# evpr_mini.net
KiCad netlist of a schematic drawn in EAGLE
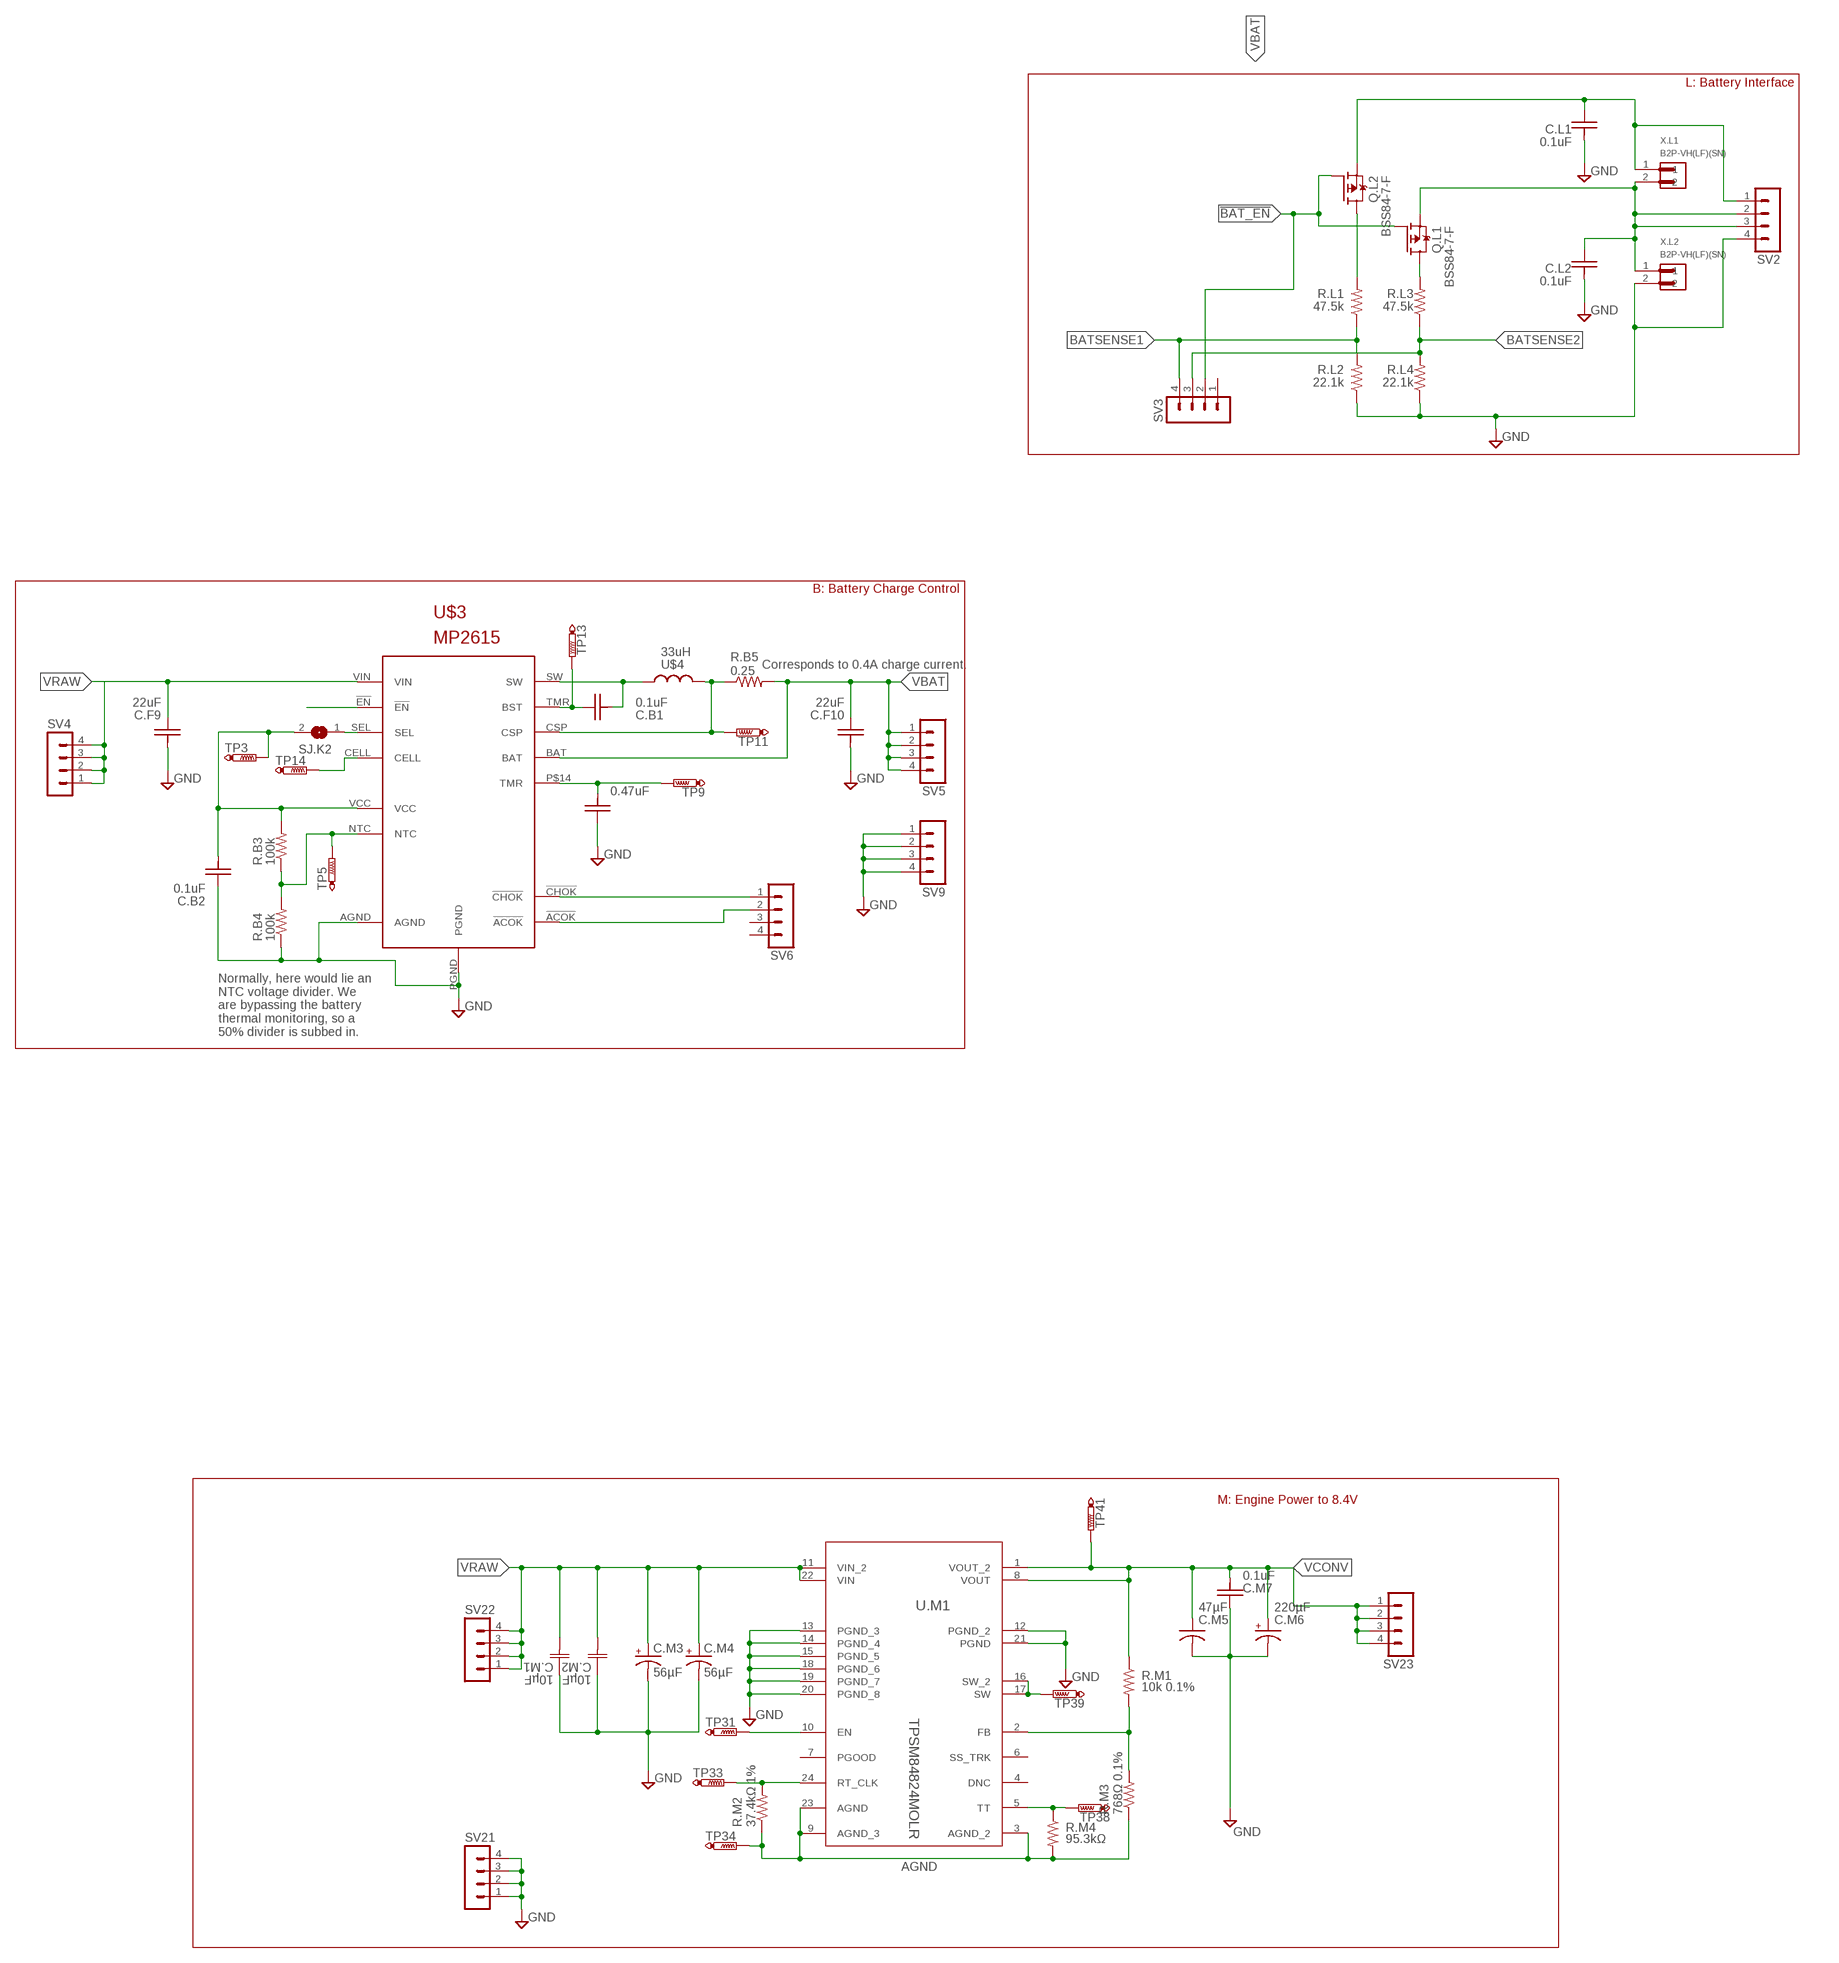
[diagram p0: schematic, sheet 1, part 1 of 2]
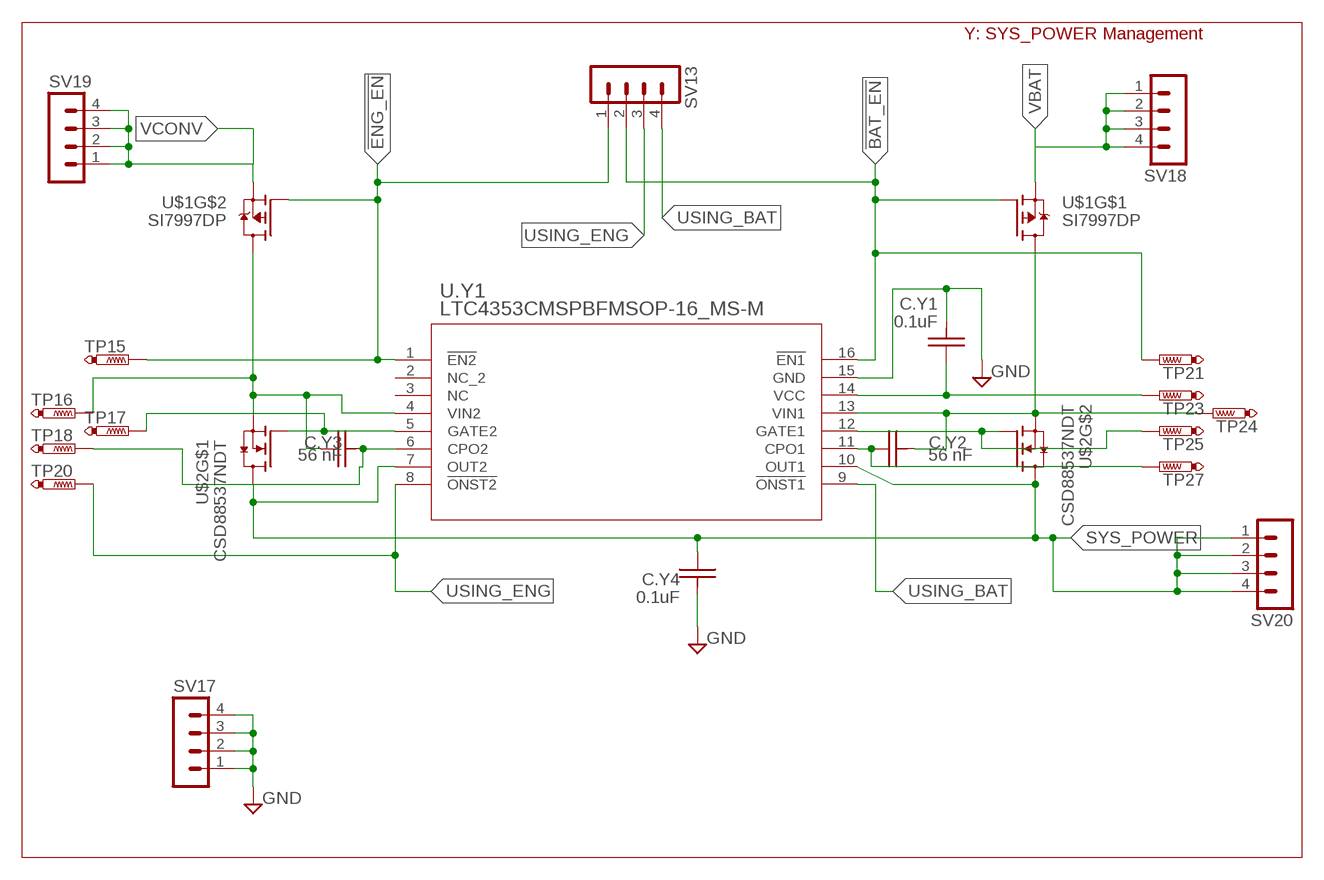
[diagram p1: schematic, sheet 1, part 2 of 2]

(export (version "E")
  (design (tool "Eeschema 10.0.6"))
  (components
    (comp (ref "C.B1")
      (value "0.1uF")
      (footprint "eagle-import:C0603")
      (libsource (lib "eagle-import") (part "C0603"))
    )
    (comp (ref "C.B2")
      (value "0.1uF")
      (footprint "eagle-import:C0603")
      (libsource (lib "eagle-import") (part "C0603"))
    )
    (comp (ref "C.F9")
      (value "22uF")
      (footprint "eagle-import:C0603")
      (libsource (lib "eagle-import") (part "C0603"))
    )
    (comp (ref "C.F10")
      (value "22uF")
      (footprint "eagle-import:C0603")
      (libsource (lib "eagle-import") (part "C0603"))
    )
    (comp (ref "C.J3")
      (value "0.47uF")
      (footprint "eagle-import:C0603")
      (libsource (lib "eagle-import") (part "C0603"))
    )
    (comp (ref "C.L1")
      (value "0.1uF")
      (footprint "eagle-import:C0603")
      (libsource (lib "eagle-import") (part "C0603"))
    )
    (comp (ref "C.L2")
      (value "0.1uF")
      (footprint "eagle-import:C0603")
      (libsource (lib "eagle-import") (part "C0603"))
    )
    (comp (ref "C.M1")
      (value "10µF")
      (footprint "eagle-import:CAP_3225")
      (libsource (lib "eagle-import") (part "C3225X7R1E106K250AC"))
    )
    (comp (ref "C.M2")
      (value "10µF")
      (footprint "eagle-import:CAP_3225")
      (libsource (lib "eagle-import") (part "C3225X7R1E106K250AC"))
    )
    (comp (ref "C.M3")
      (value "56µF")
      (footprint "eagle-import:OSCON_SVPF_6.3MM")
      (libsource (lib "eagle-import") (part "6.3MMCAP"))
    )
    (comp (ref "C.M4")
      (value "56µF")
      (footprint "eagle-import:OSCON_SVPF_6.3MM")
      (libsource (lib "eagle-import") (part "6.3MMCAP"))
    )
    (comp (ref "C.M5")
      (value "47µF")
      (footprint "eagle-import:C1210")
      (libsource (lib "eagle-import") (part "C-USC1210"))
    )
    (comp (ref "C.M6")
      (value "220µF")
      (footprint "eagle-import:C6CYLCAP")
      (libsource (lib "eagle-import") (part "WURTH875115352003"))
    )
    (comp (ref "C.M7")
      (value "0.1uF")
      (footprint "eagle-import:C0603")
      (libsource (lib "eagle-import") (part "C0603"))
    )
    (comp (ref "C.Y1")
      (value "0.1uF")
      (footprint "eagle-import:C0603")
      (libsource (lib "eagle-import") (part "C0603"))
    )
    (comp (ref "C.Y2")
      (value "56 nF")
      (footprint "eagle-import:C0603")
      (libsource (lib "eagle-import") (part "C0603"))
    )
    (comp (ref "C.Y3")
      (value "56 nF")
      (footprint "eagle-import:C0603")
      (libsource (lib "eagle-import") (part "C0603"))
    )
    (comp (ref "C.Y4")
      (value "0.1uF")
      (footprint "eagle-import:C0603")
      (libsource (lib "eagle-import") (part "C0603"))
    )
    (comp (ref "Q.L1")
      (value "BSS84-7-F")
      (footprint "eagle-import:SOT23")
      (libsource (lib "eagle-import") (part "BSS84-7-F"))
    )
    (comp (ref "Q.L2")
      (value "BSS84-7-F")
      (footprint "eagle-import:SOT23")
      (libsource (lib "eagle-import") (part "BSS84-7-F"))
    )
    (comp (ref "R.B3")
      (value "100k")
      (footprint "eagle-import:R0603")
      (libsource (lib "eagle-import") (part "R0603"))
    )
    (comp (ref "R.B4")
      (value "100k")
      (footprint "eagle-import:R0603")
      (libsource (lib "eagle-import") (part "R0603"))
    )
    (comp (ref "R.B5")
      (value "0.25")
      (footprint "eagle-import:R0603")
      (libsource (lib "eagle-import") (part "R0603"))
    )
    (comp (ref "R.L1")
      (value "47.5k")
      (footprint "eagle-import:R0603")
      (libsource (lib "eagle-import") (part "R0603"))
    )
    (comp (ref "R.L2")
      (value "22.1k")
      (footprint "eagle-import:R0603")
      (libsource (lib "eagle-import") (part "R0603"))
    )
    (comp (ref "R.L3")
      (value "47.5k")
      (footprint "eagle-import:R0603")
      (libsource (lib "eagle-import") (part "R0603"))
    )
    (comp (ref "R.L4")
      (value "22.1k")
      (footprint "eagle-import:R0603")
      (libsource (lib "eagle-import") (part "R0603"))
    )
    (comp (ref "R.M1")
      (value "10k 0.1%")
      (footprint "eagle-import:R0603")
      (libsource (lib "eagle-import") (part "R0603"))
    )
    (comp (ref "R.M2")
      (value "37.4kΩ 1%")
      (footprint "eagle-import:R0603")
      (libsource (lib "eagle-import") (part "R0603"))
    )
    (comp (ref "R.M3")
      (value "768Ω 0.1%")
      (footprint "eagle-import:R0603")
      (libsource (lib "eagle-import") (part "R0603"))
    )
    (comp (ref "R.M4")
      (value "95.3kΩ")
      (footprint "eagle-import:R0603")
      (libsource (lib "eagle-import") (part "R0603"))
    )
    (comp (ref "SJ.K2")
      (value "SJ")
      (footprint "eagle-import:SJ")
      (libsource (lib "eagle-import") (part "SJ"))
    )
    (comp (ref "SV2")
      (value "MA04-1")
      (footprint "eagle-import:MA04-1")
      (libsource (lib "eagle-import") (part "MA04-1"))
    )
    (comp (ref "SV3")
      (value "MA04-1")
      (footprint "eagle-import:MA04-1")
      (libsource (lib "eagle-import") (part "MA04-1"))
    )
    (comp (ref "SV4")
      (value "MA04-1")
      (footprint "eagle-import:MA04-1")
      (libsource (lib "eagle-import") (part "MA04-1"))
    )
    (comp (ref "SV5")
      (value "MA04-1")
      (footprint "eagle-import:MA04-1")
      (libsource (lib "eagle-import") (part "MA04-1"))
    )
    (comp (ref "SV6")
      (value "MA04-1")
      (footprint "eagle-import:MA04-1")
      (libsource (lib "eagle-import") (part "MA04-1"))
    )
    (comp (ref "SV9")
      (value "MA04-1")
      (footprint "eagle-import:MA04-1")
      (libsource (lib "eagle-import") (part "MA04-1"))
    )
    (comp (ref "SV13")
      (value "MA04-1")
      (footprint "eagle-import:MA04-1")
      (libsource (lib "eagle-import") (part "MA04-1"))
    )
    (comp (ref "SV17")
      (value "MA04-1")
      (footprint "eagle-import:MA04-1")
      (libsource (lib "eagle-import") (part "MA04-1"))
    )
    (comp (ref "SV18")
      (value "MA04-1")
      (footprint "eagle-import:MA04-1")
      (libsource (lib "eagle-import") (part "MA04-1"))
    )
    (comp (ref "SV19")
      (value "MA04-1")
      (footprint "eagle-import:MA04-1")
      (libsource (lib "eagle-import") (part "MA04-1"))
    )
    (comp (ref "SV20")
      (value "MA04-1")
      (footprint "eagle-import:MA04-1")
      (libsource (lib "eagle-import") (part "MA04-1"))
    )
    (comp (ref "SV21")
      (value "MA04-1")
      (footprint "eagle-import:MA04-1")
      (libsource (lib "eagle-import") (part "MA04-1"))
    )
    (comp (ref "SV22")
      (value "MA04-1")
      (footprint "eagle-import:MA04-1")
      (libsource (lib "eagle-import") (part "MA04-1"))
    )
    (comp (ref "SV23")
      (value "MA04-1")
      (footprint "eagle-import:MA04-1")
      (libsource (lib "eagle-import") (part "MA04-1"))
    )
    (comp (ref "TP3")
      (value "PTR1TP10R")
      (footprint "eagle-import:TP10R")
      (libsource (lib "eagle-import") (part "PTR1TP10R"))
    )
    (comp (ref "TP5")
      (value "PTR1TP10R")
      (footprint "eagle-import:TP10R")
      (libsource (lib "eagle-import") (part "PTR1TP10R"))
    )
    (comp (ref "TP9")
      (value "PTR1TP10R")
      (footprint "eagle-import:TP10R")
      (libsource (lib "eagle-import") (part "PTR1TP10R"))
    )
    (comp (ref "TP11")
      (value "PTR1TP10R")
      (footprint "eagle-import:TP10R")
      (libsource (lib "eagle-import") (part "PTR1TP10R"))
    )
    (comp (ref "TP13")
      (value "PTR1TP10R")
      (footprint "eagle-import:TP10R")
      (libsource (lib "eagle-import") (part "PTR1TP10R"))
    )
    (comp (ref "TP14")
      (value "PTR1TP10R")
      (footprint "eagle-import:TP10R")
      (libsource (lib "eagle-import") (part "PTR1TP10R"))
    )
    (comp (ref "TP15")
      (value "PTR1TP10R")
      (footprint "eagle-import:TP10R")
      (libsource (lib "eagle-import") (part "PTR1TP10R"))
    )
    (comp (ref "TP16")
      (value "PTR1TP10R")
      (footprint "eagle-import:TP10R")
      (libsource (lib "eagle-import") (part "PTR1TP10R"))
    )
    (comp (ref "TP17")
      (value "PTR1TP10R")
      (footprint "eagle-import:TP10R")
      (libsource (lib "eagle-import") (part "PTR1TP10R"))
    )
    (comp (ref "TP18")
      (value "PTR1TP10R")
      (footprint "eagle-import:TP10R")
      (libsource (lib "eagle-import") (part "PTR1TP10R"))
    )
    (comp (ref "TP20")
      (value "PTR1TP10R")
      (footprint "eagle-import:TP10R")
      (libsource (lib "eagle-import") (part "PTR1TP10R"))
    )
    (comp (ref "TP21")
      (value "PTR1TP10R")
      (footprint "eagle-import:TP10R")
      (libsource (lib "eagle-import") (part "PTR1TP10R"))
    )
    (comp (ref "TP23")
      (value "PTR1TP10R")
      (footprint "eagle-import:TP10R")
      (libsource (lib "eagle-import") (part "PTR1TP10R"))
    )
    (comp (ref "TP24")
      (value "PTR1TP10R")
      (footprint "eagle-import:TP10R")
      (libsource (lib "eagle-import") (part "PTR1TP10R"))
    )
    (comp (ref "TP25")
      (value "PTR1TP10R")
      (footprint "eagle-import:TP10R")
      (libsource (lib "eagle-import") (part "PTR1TP10R"))
    )
    (comp (ref "TP27")
      (value "PTR1TP10R")
      (footprint "eagle-import:TP10R")
      (libsource (lib "eagle-import") (part "PTR1TP10R"))
    )
    (comp (ref "TP31")
      (value "PTR1TP10R")
      (footprint "eagle-import:TP10R")
      (libsource (lib "eagle-import") (part "PTR1TP10R"))
    )
    (comp (ref "TP33")
      (value "PTR1TP10R")
      (footprint "eagle-import:TP10R")
      (libsource (lib "eagle-import") (part "PTR1TP10R"))
    )
    (comp (ref "TP34")
      (value "PTR1TP10R")
      (footprint "eagle-import:TP10R")
      (libsource (lib "eagle-import") (part "PTR1TP10R"))
    )
    (comp (ref "TP38")
      (value "PTR1TP10R")
      (footprint "eagle-import:TP10R")
      (libsource (lib "eagle-import") (part "PTR1TP10R"))
    )
    (comp (ref "TP39")
      (value "PTR1TP10R")
      (footprint "eagle-import:TP10R")
      (libsource (lib "eagle-import") (part "PTR1TP10R"))
    )
    (comp (ref "TP41")
      (value "PTR1TP10R")
      (footprint "eagle-import:TP10R")
      (libsource (lib "eagle-import") (part "PTR1TP10R"))
    )
    (comp (ref "U$1")
      (value "SI7997DP")
      (footprint "eagle-import:POWERPAK_SO8DUAL")
      (libsource (lib "eagle-import") (part "SI7997DP"))
    )
    (comp (ref "U$2")
      (value "CSD88537NDT")
      (footprint "eagle-import:SOIC8")
      (libsource (lib "eagle-import") (part "CSD88537NDT"))
    )
    (comp (ref "U$3")
      (value "MP2615")
      (footprint "eagle-import:QFN16")
      (libsource (lib "eagle-import") (part "MP2615"))
    )
    (comp (ref "U$4")
      (value "33uH")
      (footprint "eagle-import:SRN5040TA")
      (libsource (lib "eagle-import") (part "SRN5040TA-330M"))
    )
    (comp (ref "U.M1")
      (value "TPSM84824MOLR")
      (footprint "eagle-import:MOL0024A")
      (libsource (lib "eagle-import") (part "TPSM84824MOLR"))
    )
    (comp (ref "U.Y1")
      (value "LTC4353CMSPBFMSOP-16_MS-M")
      (footprint "eagle-import:MSOP-16_MS-M")
      (fields (field (name "MANUFACTURER_PART_NUMBER") "LTC4353CMS#PBF"))
      (libsource (lib "eagle-import") (part "LTC4353CMSPBFMSOP-16_MS-M"))
    )
    (comp (ref "X.L1")
      (value "B2P-VH(LF)(SN)")
      (footprint "eagle-import:JST_B2P-VH(LF)(SN)")
      (fields (field (name "MF") "JST Sales") (field (name "MP") "B2P-VH_LF__SN_"))
      (libsource (lib "eagle-import") (part "B2P-VH(LF)(SN)"))
    )
    (comp (ref "X.L2")
      (value "B2P-VH(LF)(SN)")
      (footprint "eagle-import:JST_B2P-VH(LF)(SN)")
      (fields (field (name "MF") "JST Sales") (field (name "MP") "B2P-VH_LF__SN_"))
      (libsource (lib "eagle-import") (part "B2P-VH(LF)(SN)"))
    )
  )
  (nets
    (net (code "1") (name "/AGND") (class "Default")
      (node (ref "R.M2") (pin "1") (pinfunction "1_1") (pintype "passive"))
      (node (ref "R.M3") (pin "1") (pinfunction "1_1") (pintype "passive"))
      (node (ref "R.M4") (pin "2") (pinfunction "2_2") (pintype "passive"))
      (node (ref "TP34") (pin "TP") (pinfunction "TP_TP") (pintype "input"))
      (node (ref "U.M1") (pin "23") (pinfunction "AGND_23") (pintype "power_in"))
      (node (ref "U.M1") (pin "3") (pinfunction "AGND_2_3") (pintype "power_in"))
      (node (ref "U.M1") (pin "9") (pinfunction "AGND_3_9") (pintype "power_in"))
    )
    (net (code "2") (name "/~{BAT_EN}") (class "Default")
      (node (ref "Q.L1") (pin "1") (pinfunction "G_1") (pintype "passive"))
      (node (ref "Q.L2") (pin "1") (pinfunction "G_1") (pintype "passive"))
      (node (ref "SV13") (pin "2") (pinfunction "2_2") (pintype "passive"))
      (node (ref "SV3") (pin "2") (pinfunction "2_2") (pintype "passive"))
      (node (ref "TP21") (pin "TP") (pinfunction "TP_TP") (pintype "input"))
      (node (ref "U$1") (pin "P$2") (pinfunction "G_P$2") (pintype "passive"))
      (node (ref "U.Y1") (pin "16") (pinfunction "~{EN1}_16") (pintype "input"))
    )
    (net (code "3") (name "/~{ENG_EN}") (class "Default")
      (node (ref "SV13") (pin "1") (pinfunction "1_1") (pintype "passive"))
      (node (ref "TP15") (pin "TP") (pinfunction "TP_TP") (pintype "input"))
      (node (ref "U$1") (pin "P$4") (pinfunction "G_P$4") (pintype "passive"))
      (node (ref "U.Y1") (pin "1") (pinfunction "~{EN2}_1") (pintype "input"))
    )
    (net (code "4") (name "BATSENSE1") (class "Default")
      (node (ref "R.L1") (pin "1") (pinfunction "1_1") (pintype "passive"))
      (node (ref "R.L2") (pin "2") (pinfunction "2_2") (pintype "passive"))
      (node (ref "SV3") (pin "4") (pinfunction "4_4") (pintype "passive"))
    )
    (net (code "5") (name "BATSENSE2") (class "Default")
      (node (ref "R.L3") (pin "1") (pinfunction "1_1") (pintype "passive"))
      (node (ref "R.L4") (pin "2") (pinfunction "2_2") (pintype "passive"))
      (node (ref "SV3") (pin "3") (pinfunction "3_3") (pintype "passive"))
    )
    (net (code "6") (name "GND") (class "Default")
      (node (ref "C.B2") (pin "1") (pinfunction "1_1") (pintype "passive"))
      (node (ref "C.F10") (pin "2") (pinfunction "2_2") (pintype "passive"))
      (node (ref "C.F9") (pin "2") (pinfunction "2_2") (pintype "passive"))
      (node (ref "C.J3") (pin "1") (pinfunction "1_1") (pintype "passive"))
      (node (ref "C.L1") (pin "2") (pinfunction "2_2") (pintype "passive"))
      (node (ref "C.L2") (pin "2") (pinfunction "2_2") (pintype "passive"))
      (node (ref "C.M1") (pin "1") (pinfunction "1_1") (pintype "passive"))
      (node (ref "C.M2") (pin "1") (pinfunction "1_1") (pintype "passive"))
      (node (ref "C.M3") (pin "-") (pinfunction "-_-") (pintype "passive"))
      (node (ref "C.M4") (pin "-") (pinfunction "-_-") (pintype "passive"))
      (node (ref "C.M5") (pin "2") (pinfunction "2_2") (pintype "passive"))
      (node (ref "C.M6") (pin "P$1") (pinfunction "-_P$1") (pintype "passive"))
      (node (ref "C.M7") (pin "1") (pinfunction "1_1") (pintype "passive"))
      (node (ref "C.Y1") (pin "2") (pinfunction "2_2") (pintype "passive"))
      (node (ref "C.Y4") (pin "2") (pinfunction "2_2") (pintype "passive"))
      (node (ref "R.B4") (pin "1") (pinfunction "1_1") (pintype "passive"))
      (node (ref "R.L2") (pin "1") (pinfunction "1_1") (pintype "passive"))
      (node (ref "R.L4") (pin "1") (pinfunction "1_1") (pintype "passive"))
      (node (ref "SV17") (pin "1") (pinfunction "1_1") (pintype "passive"))
      (node (ref "SV17") (pin "2") (pinfunction "2_2") (pintype "passive"))
      (node (ref "SV17") (pin "3") (pinfunction "3_3") (pintype "passive"))
      (node (ref "SV17") (pin "4") (pinfunction "4_4") (pintype "passive"))
      (node (ref "SV2") (pin "4") (pinfunction "4_4") (pintype "passive"))
      (node (ref "SV21") (pin "1") (pinfunction "1_1") (pintype "passive"))
      (node (ref "SV21") (pin "2") (pinfunction "2_2") (pintype "passive"))
      (node (ref "SV21") (pin "3") (pinfunction "3_3") (pintype "passive"))
      (node (ref "SV21") (pin "4") (pinfunction "4_4") (pintype "passive"))
      (node (ref "SV9") (pin "1") (pinfunction "1_1") (pintype "passive"))
      (node (ref "SV9") (pin "2") (pinfunction "2_2") (pintype "passive"))
      (node (ref "SV9") (pin "3") (pinfunction "3_3") (pintype "passive"))
      (node (ref "SV9") (pin "4") (pinfunction "4_4") (pintype "passive"))
      (node (ref "U$3") (pin "AGND") (pinfunction "AGND_AGND") (pintype "bidirectional"))
      (node (ref "U$3") (pin "PGND") (pinfunction "PGND_PGND") (pintype "bidirectional"))
      (node (ref "U.M1") (pin "12") (pinfunction "PGND_2_12") (pintype "power_in"))
      (node (ref "U.M1") (pin "13") (pinfunction "PGND_3_13") (pintype "power_in"))
      (node (ref "U.M1") (pin "14") (pinfunction "PGND_4_14") (pintype "power_in"))
      (node (ref "U.M1") (pin "15") (pinfunction "PGND_5_15") (pintype "power_in"))
      (node (ref "U.M1") (pin "18") (pinfunction "PGND_6_18") (pintype "power_in"))
      (node (ref "U.M1") (pin "19") (pinfunction "PGND_7_19") (pintype "power_in"))
      (node (ref "U.M1") (pin "20") (pinfunction "PGND_8_20") (pintype "power_in"))
      (node (ref "U.M1") (pin "21") (pinfunction "PGND_21") (pintype "power_in"))
      (node (ref "U.Y1") (pin "15") (pinfunction "GND_15") (pintype "power_in"))
      (node (ref "X.L2") (pin "2") (pinfunction "2_2") (pintype "passive"))
    )
    (net (code "7") (name "Net-(C.B2-Pad2)") (class "Default")
      (node (ref "C.B2") (pin "2") (pinfunction "2_2") (pintype "passive"))
      (node (ref "R.B3") (pin "2") (pinfunction "2_2") (pintype "passive"))
      (node (ref "SJ.K2") (pin "2") (pinfunction "2_2") (pintype "passive"))
      (node (ref "TP3") (pin "TP") (pinfunction "TP_TP") (pintype "input"))
      (node (ref "U$3") (pin "VCC") (pinfunction "VCC_VCC") (pintype "bidirectional"))
    )
    (net (code "8") (name "Net-(Q.L1-D)") (class "Default")
      (node (ref "Q.L1") (pin "3") (pinfunction "D_3") (pintype "passive"))
      (node (ref "R.L3") (pin "2") (pinfunction "2_2") (pintype "passive"))
    )
    (net (code "9") (name "Net-(Q.L1-S)") (class "Default")
      (node (ref "C.L2") (pin "1") (pinfunction "1_1") (pintype "passive"))
      (node (ref "Q.L1") (pin "2") (pinfunction "S_2") (pintype "passive"))
      (node (ref "SV2") (pin "2") (pinfunction "2_2") (pintype "passive"))
      (node (ref "SV2") (pin "3") (pinfunction "3_3") (pintype "passive"))
      (node (ref "X.L1") (pin "2") (pinfunction "2_2") (pintype "passive"))
      (node (ref "X.L2") (pin "1") (pinfunction "1_1") (pintype "passive"))
    )
    (net (code "10") (name "Net-(Q.L2-D)") (class "Default")
      (node (ref "Q.L2") (pin "3") (pinfunction "D_3") (pintype "passive"))
      (node (ref "R.L1") (pin "2") (pinfunction "2_2") (pintype "passive"))
    )
    (net (code "11") (name "Net-(R.B3-Pad1)") (class "Default")
      (node (ref "R.B3") (pin "1") (pinfunction "1_1") (pintype "passive"))
      (node (ref "R.B4") (pin "2") (pinfunction "2_2") (pintype "passive"))
      (node (ref "TP5") (pin "TP") (pinfunction "TP_TP") (pintype "input"))
      (node (ref "U$3") (pin "NTC") (pinfunction "NTC_NTC") (pintype "bidirectional"))
    )
    (net (code "12") (name "Net-(SJ.K2-Pad1)") (class "Default")
      (node (ref "SJ.K2") (pin "1") (pinfunction "1_1") (pintype "passive"))
      (node (ref "U$3") (pin "SEL") (pinfunction "SEL_SEL") (pintype "bidirectional"))
    )
    (net (code "13") (name "Net-(TP14-PadTP)") (class "Default")
      (node (ref "TP14") (pin "TP") (pinfunction "TP_TP") (pintype "input"))
      (node (ref "U$3") (pin "CELL") (pinfunction "CELL_CELL") (pintype "bidirectional"))
    )
    (net (code "14") (name "Net-(U$1A-D)") (class "Default")
      (node (ref "C.Y2") (pin "2") (pinfunction "2_2") (pintype "passive"))
      (node (ref "TP24") (pin "TP") (pinfunction "TP_TP") (pintype "input"))
      (node (ref "U$1") (pin "D$1B") (pinfunction "D_D$1B") (pintype "passive"))
      (node (ref "U$2") (pin "3") (pinfunction "S_3") (pintype "passive"))
      (node (ref "U.Y1") (pin "13") (pinfunction "VIN1_13") (pintype "input"))
    )
    (net (code "15") (name "Net-(U$1B-D)") (class "Default")
      (node (ref "C.Y3") (pin "1") (pinfunction "1_1") (pintype "passive"))
      (node (ref "TP16") (pin "TP") (pinfunction "TP_TP") (pintype "input"))
      (node (ref "U$1") (pin "D$2A") (pinfunction "D_D$2A") (pintype "passive"))
      (node (ref "U$2") (pin "1") (pinfunction "S_1") (pintype "passive"))
      (node (ref "U.Y1") (pin "4") (pinfunction "VIN2_4") (pintype "input"))
    )
    (net (code "16") (name "Net-(U$2A-G)") (class "Default")
      (node (ref "TP17") (pin "TP") (pinfunction "TP_TP") (pintype "input"))
      (node (ref "U$2") (pin "2") (pinfunction "G_2") (pintype "passive"))
      (node (ref "U.Y1") (pin "5") (pinfunction "GATE2_5") (pintype "output"))
    )
    (net (code "17") (name "Net-(U$2B-G)") (class "Default")
      (node (ref "TP25") (pin "TP") (pinfunction "TP_TP") (pintype "input"))
      (node (ref "U$2") (pin "4") (pinfunction "G_4") (pintype "passive"))
      (node (ref "U.Y1") (pin "12") (pinfunction "GATE1_12") (pintype "output"))
    )
    (net (code "18") (name "Net-(U$3-BST)") (class "Default")
      (node (ref "C.B1") (pin "1") (pinfunction "1_1") (pintype "passive"))
      (node (ref "TP13") (pin "TP") (pinfunction "TP_TP") (pintype "input"))
      (node (ref "U$3") (pin "TMR") (pinfunction "BST_TMR") (pintype "bidirectional"))
    )
    (net (code "19") (name "Net-(U$3-TMR)") (class "Default")
      (node (ref "C.J3") (pin "2") (pinfunction "2_2") (pintype "passive"))
      (node (ref "TP9") (pin "TP") (pinfunction "TP_TP") (pintype "input"))
      (node (ref "U$3") (pin "P$14") (pinfunction "TMR_P$14") (pintype "bidirectional"))
    )
    (net (code "20") (name "Net-(U$3-~{ACOK})") (class "Default")
      (node (ref "SV6") (pin "2") (pinfunction "2_2") (pintype "passive"))
      (node (ref "U$3") (pin "!ACOK") (pinfunction "~{ACOK}_!ACOK") (pintype "bidirectional"))
    )
    (net (code "21") (name "Net-(U$3-~{CHOK})") (class "Default")
      (node (ref "SV6") (pin "1") (pinfunction "1_1") (pintype "passive"))
      (node (ref "U$3") (pin "!CHOK") (pinfunction "~{CHOK}_!CHOK") (pintype "bidirectional"))
    )
    (net (code "22") (name "Net-(U$4-1)") (class "Default")
      (node (ref "C.B1") (pin "2") (pinfunction "2_2") (pintype "passive"))
      (node (ref "U$3") (pin "SW") (pinfunction "SW_SW") (pintype "bidirectional"))
      (node (ref "U$4") (pin "P$1") (pinfunction "1_P$1") (pintype "passive"))
    )
    (net (code "23") (name "Net-(U$4-2)") (class "Default")
      (node (ref "R.B5") (pin "1") (pinfunction "1_1") (pintype "passive"))
      (node (ref "TP11") (pin "TP") (pinfunction "TP_TP") (pintype "input"))
      (node (ref "U$3") (pin "CSP") (pinfunction "CSP_CSP") (pintype "bidirectional"))
      (node (ref "U$4") (pin "P$2") (pinfunction "2_P$2") (pintype "passive"))
    )
    (net (code "24") (name "Net-(U.M1-EN)") (class "Default")
      (node (ref "TP31") (pin "TP") (pinfunction "TP_TP") (pintype "input"))
      (node (ref "U.M1") (pin "10") (pinfunction "EN_10") (pintype "input"))
    )
    (net (code "25") (name "Net-(U.M1-FB)") (class "Default")
      (node (ref "R.M1") (pin "2") (pinfunction "2_2") (pintype "passive"))
      (node (ref "R.M3") (pin "2") (pinfunction "2_2") (pintype "passive"))
      (node (ref "U.M1") (pin "2") (pinfunction "FB_2") (pintype "input"))
    )
    (net (code "26") (name "Net-(U.M1-RT_CLK)") (class "Default")
      (node (ref "R.M2") (pin "2") (pinfunction "2_2") (pintype "passive"))
      (node (ref "TP33") (pin "TP") (pinfunction "TP_TP") (pintype "input"))
      (node (ref "U.M1") (pin "24") (pinfunction "RT_CLK_24") (pintype "input"))
    )
    (net (code "27") (name "Net-(U.M1-SW)") (class "Default")
      (node (ref "TP39") (pin "TP") (pinfunction "TP_TP") (pintype "input"))
      (node (ref "U.M1") (pin "16") (pinfunction "SW_2_16") (pintype "output"))
      (node (ref "U.M1") (pin "17") (pinfunction "SW_17") (pintype "output"))
    )
    (net (code "28") (name "Net-(U.M1-TT)") (class "Default")
      (node (ref "R.M4") (pin "1") (pinfunction "1_1") (pintype "passive"))
      (node (ref "TP38") (pin "TP") (pinfunction "TP_TP") (pintype "input"))
      (node (ref "U.M1") (pin "5") (pinfunction "TT_5") (pintype "passive"))
    )
    (net (code "29") (name "Net-(U.Y1-CPO1)") (class "Default")
      (node (ref "C.Y2") (pin "1") (pinfunction "1_1") (pintype "passive"))
      (node (ref "TP27") (pin "TP") (pinfunction "TP_TP") (pintype "input"))
      (node (ref "U.Y1") (pin "11") (pinfunction "CPO1_11") (pintype "output"))
    )
    (net (code "30") (name "Net-(U.Y1-CPO2)") (class "Default")
      (node (ref "C.Y3") (pin "2") (pinfunction "2_2") (pintype "passive"))
      (node (ref "TP18") (pin "TP") (pinfunction "TP_TP") (pintype "input"))
      (node (ref "U.Y1") (pin "6") (pinfunction "CPO2_6") (pintype "output"))
    )
    (net (code "31") (name "Net-(U.Y1-VCC)") (class "Default")
      (node (ref "C.Y1") (pin "1") (pinfunction "1_1") (pintype "passive"))
      (node (ref "TP23") (pin "TP") (pinfunction "TP_TP") (pintype "input"))
      (node (ref "U.Y1") (pin "14") (pinfunction "VCC_14") (pintype "power_in"))
    )
    (net (code "32") (name "SYS_POWER") (class "Default")
      (node (ref "C.Y4") (pin "1") (pinfunction "1_1") (pintype "passive"))
      (node (ref "SV20") (pin "1") (pinfunction "1_1") (pintype "passive"))
      (node (ref "SV20") (pin "2") (pinfunction "2_2") (pintype "passive"))
      (node (ref "SV20") (pin "3") (pinfunction "3_3") (pintype "passive"))
      (node (ref "SV20") (pin "4") (pinfunction "4_4") (pintype "passive"))
      (node (ref "U$2") (pin "5") (pinfunction "D_5") (pintype "passive"))
      (node (ref "U$2") (pin "6") (pinfunction "D_6") (pintype "passive"))
      (node (ref "U$2") (pin "7") (pinfunction "D_7") (pintype "passive"))
      (node (ref "U$2") (pin "8") (pinfunction "D_8") (pintype "passive"))
      (node (ref "U.Y1") (pin "10") (pinfunction "OUT1_10") (pintype "output"))
      (node (ref "U.Y1") (pin "7") (pinfunction "OUT2_7") (pintype "output"))
    )
    (net (code "33") (name "USING_BAT") (class "Default")
      (node (ref "SV13") (pin "4") (pinfunction "4_4") (pintype "passive"))
      (node (ref "U.Y1") (pin "9") (pinfunction "~{ONST1}_9") (pintype "output"))
    )
    (net (code "34") (name "USING_ENG") (class "Default")
      (node (ref "SV13") (pin "3") (pinfunction "3_3") (pintype "passive"))
      (node (ref "TP20") (pin "TP") (pinfunction "TP_TP") (pintype "input"))
      (node (ref "U.Y1") (pin "8") (pinfunction "~{ONST2}_8") (pintype "output"))
    )
    (net (code "35") (name "VBAT") (class "Default")
      (node (ref "C.F10") (pin "1") (pinfunction "1_1") (pintype "passive"))
      (node (ref "C.L1") (pin "1") (pinfunction "1_1") (pintype "passive"))
      (node (ref "Q.L2") (pin "2") (pinfunction "S_2") (pintype "passive"))
      (node (ref "R.B5") (pin "2") (pinfunction "2_2") (pintype "passive"))
      (node (ref "SV18") (pin "1") (pinfunction "1_1") (pintype "passive"))
      (node (ref "SV18") (pin "2") (pinfunction "2_2") (pintype "passive"))
      (node (ref "SV18") (pin "3") (pinfunction "3_3") (pintype "passive"))
      (node (ref "SV18") (pin "4") (pinfunction "4_4") (pintype "passive"))
      (node (ref "SV2") (pin "1") (pinfunction "1_1") (pintype "passive"))
      (node (ref "SV5") (pin "1") (pinfunction "1_1") (pintype "passive"))
      (node (ref "SV5") (pin "2") (pinfunction "2_2") (pintype "passive"))
      (node (ref "SV5") (pin "3") (pinfunction "3_3") (pintype "passive"))
      (node (ref "SV5") (pin "4") (pinfunction "4_4") (pintype "passive"))
      (node (ref "U$1") (pin "P$1") (pinfunction "S_P$1") (pintype "passive"))
      (node (ref "U$3") (pin "BAT") (pinfunction "BAT_BAT") (pintype "bidirectional"))
      (node (ref "X.L1") (pin "1") (pinfunction "1_1") (pintype "passive"))
    )
    (net (code "36") (name "VCONV") (class "Default")
      (node (ref "C.M5") (pin "1") (pinfunction "1_1") (pintype "passive"))
      (node (ref "C.M6") (pin "P$2") (pinfunction "+_P$2") (pintype "passive"))
      (node (ref "C.M7") (pin "2") (pinfunction "2_2") (pintype "passive"))
      (node (ref "R.M1") (pin "1") (pinfunction "1_1") (pintype "passive"))
      (node (ref "SV19") (pin "1") (pinfunction "1_1") (pintype "passive"))
      (node (ref "SV19") (pin "2") (pinfunction "2_2") (pintype "passive"))
      (node (ref "SV19") (pin "3") (pinfunction "3_3") (pintype "passive"))
      (node (ref "SV19") (pin "4") (pinfunction "4_4") (pintype "passive"))
      (node (ref "SV23") (pin "1") (pinfunction "1_1") (pintype "passive"))
      (node (ref "SV23") (pin "2") (pinfunction "2_2") (pintype "passive"))
      (node (ref "SV23") (pin "3") (pinfunction "3_3") (pintype "passive"))
      (node (ref "SV23") (pin "4") (pinfunction "4_4") (pintype "passive"))
      (node (ref "TP41") (pin "TP") (pinfunction "TP_TP") (pintype "input"))
      (node (ref "U$1") (pin "P$3") (pinfunction "S_P$3") (pintype "passive"))
      (node (ref "U.M1") (pin "1") (pinfunction "VOUT_2_1") (pintype "power_in"))
      (node (ref "U.M1") (pin "8") (pinfunction "VOUT_8") (pintype "power_in"))
    )
    (net (code "37") (name "VRAW") (class "Default")
      (node (ref "C.F9") (pin "1") (pinfunction "1_1") (pintype "passive"))
      (node (ref "C.M1") (pin "2") (pinfunction "2_2") (pintype "passive"))
      (node (ref "C.M2") (pin "2") (pinfunction "2_2") (pintype "passive"))
      (node (ref "C.M3") (pin "+") (pinfunction "+_+") (pintype "passive"))
      (node (ref "C.M4") (pin "+") (pinfunction "+_+") (pintype "passive"))
      (node (ref "SV22") (pin "1") (pinfunction "1_1") (pintype "passive"))
      (node (ref "SV22") (pin "2") (pinfunction "2_2") (pintype "passive"))
      (node (ref "SV22") (pin "3") (pinfunction "3_3") (pintype "passive"))
      (node (ref "SV22") (pin "4") (pinfunction "4_4") (pintype "passive"))
      (node (ref "SV4") (pin "1") (pinfunction "1_1") (pintype "passive"))
      (node (ref "SV4") (pin "2") (pinfunction "2_2") (pintype "passive"))
      (node (ref "SV4") (pin "3") (pinfunction "3_3") (pintype "passive"))
      (node (ref "SV4") (pin "4") (pinfunction "4_4") (pintype "passive"))
      (node (ref "U$3") (pin "VIN") (pinfunction "VIN_VIN") (pintype "bidirectional"))
      (node (ref "U.M1") (pin "11") (pinfunction "VIN_2_11") (pintype "power_in"))
      (node (ref "U.M1") (pin "22") (pinfunction "VIN_22") (pintype "power_in"))
    )
    (net (code "38") (name "unconnected-(SV3-Pad1)") (class "Default")
      (node (ref "SV3") (pin "1") (pinfunction "1_1") (pintype "passive"))
    )
    (net (code "39") (name "unconnected-(SV6-Pad3)") (class "Default")
      (node (ref "SV6") (pin "3") (pinfunction "3_3") (pintype "passive"))
    )
    (net (code "40") (name "unconnected-(SV6-Pad4)") (class "Default")
      (node (ref "SV6") (pin "4") (pinfunction "4_4") (pintype "passive"))
    )
    (net (code "41") (name "unconnected-(U$3-~{EN}-Pad!EN)") (class "Default")
      (node (ref "U$3") (pin "!EN") (pinfunction "~{EN}_!EN") (pintype "bidirectional"))
    )
    (net (code "42") (name "unconnected-(U.M1-DNC-Pad4)") (class "Default")
      (node (ref "U.M1") (pin "4") (pinfunction "DNC_4") (pintype "passive"))
    )
    (net (code "43") (name "unconnected-(U.M1-PGOOD-Pad7)") (class "Default")
      (node (ref "U.M1") (pin "7") (pinfunction "PGOOD_7") (pintype "passive"))
    )
    (net (code "44") (name "unconnected-(U.M1-SS_TRK-Pad6)") (class "Default")
      (node (ref "U.M1") (pin "6") (pinfunction "SS_TRK_6") (pintype "passive"))
    )
    (net (code "45") (name "unconnected-(U.Y1-NC-Pad3)") (class "Default")
      (node (ref "U.Y1") (pin "3") (pinfunction "NC_3") (pintype "no_connect"))
    )
    (net (code "46") (name "unconnected-(U.Y1-NC_2-Pad2)") (class "Default")
      (node (ref "U.Y1") (pin "2") (pinfunction "NC_2_2") (pintype "no_connect"))
    )
  )
)
